# OLD_REGENIX_Relais.net
KiCad netlist of a schematic drawn in Altium Designer
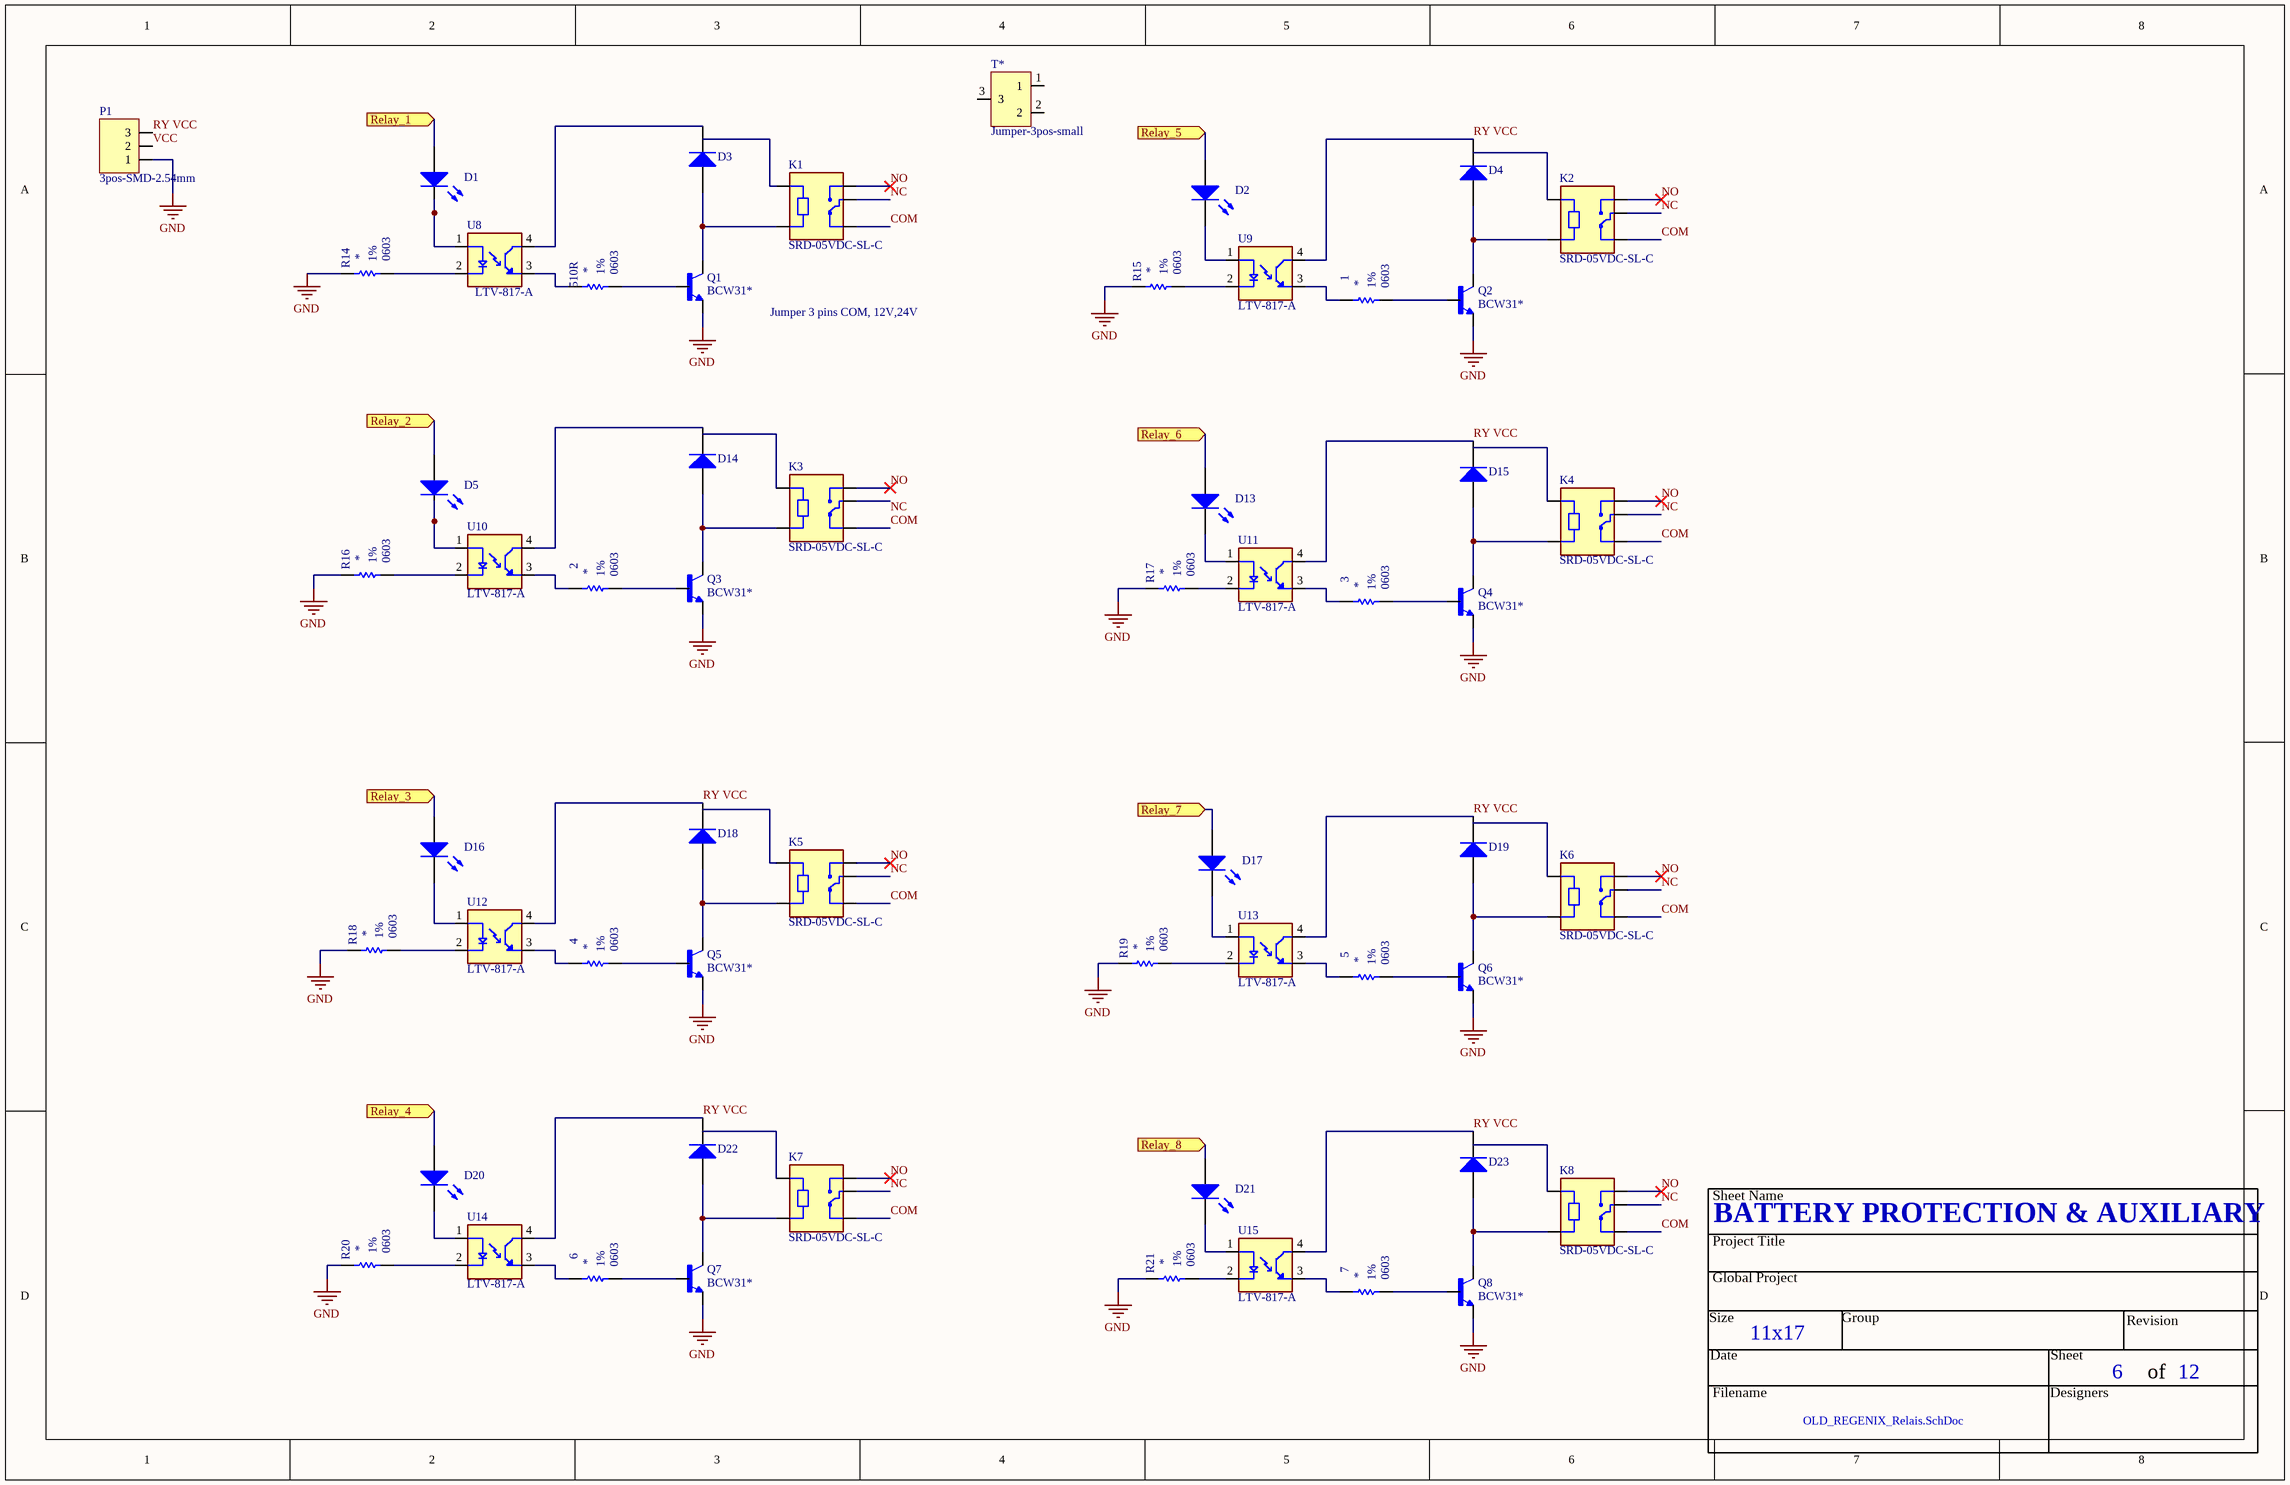
[diagram p0: OLD_REGENIX_Relais.SchDoc]

(export (version "E")
  (design (tool "Eeschema 10.0.6"))
  (components
    (comp (ref "1")
      (value "RES - 0603")
      (footprint "RES_0603")
      (fields
        (field (name "PACKAGE") "0603")
        (field (name "PRECISION") "1%")
        (field (name "ALTIUM_VALUE") "*")
        (field (name "CREATEDBY") "Jonathan Bouchard")
      )
      (libsource (lib "S7CAS_LIB2023") (part "RES - 0603"))
    )
    (comp (ref "2")
      (value "RES - 0603")
      (footprint "RES_0603")
      (fields
        (field (name "PACKAGE") "0603")
        (field (name "PRECISION") "1%")
        (field (name "ALTIUM_VALUE") "*")
        (field (name "CREATEDBY") "Jonathan Bouchard")
      )
      (libsource (lib "S7CAS_LIB2023") (part "RES - 0603"))
    )
    (comp (ref "3")
      (value "RES - 0603")
      (footprint "RES_0603")
      (fields
        (field (name "PACKAGE") "0603")
        (field (name "PRECISION") "1%")
        (field (name "ALTIUM_VALUE") "*")
        (field (name "CREATEDBY") "Jonathan Bouchard")
      )
      (libsource (lib "S7CAS_LIB2023") (part "RES - 0603"))
    )
    (comp (ref "4")
      (value "RES - 0603")
      (footprint "RES_0603")
      (fields
        (field (name "PACKAGE") "0603")
        (field (name "PRECISION") "1%")
        (field (name "ALTIUM_VALUE") "*")
        (field (name "CREATEDBY") "Jonathan Bouchard")
      )
      (libsource (lib "S7CAS_LIB2023") (part "RES - 0603"))
    )
    (comp (ref "5")
      (value "RES - 0603")
      (footprint "RES_0603")
      (fields
        (field (name "PACKAGE") "0603")
        (field (name "PRECISION") "1%")
        (field (name "ALTIUM_VALUE") "*")
        (field (name "CREATEDBY") "Jonathan Bouchard")
      )
      (libsource (lib "S7CAS_LIB2023") (part "RES - 0603"))
    )
    (comp (ref "6")
      (value "RES - 0603")
      (footprint "RES_0603")
      (fields
        (field (name "PACKAGE") "0603")
        (field (name "PRECISION") "1%")
        (field (name "ALTIUM_VALUE") "*")
        (field (name "CREATEDBY") "Jonathan Bouchard")
      )
      (libsource (lib "S7CAS_LIB2023") (part "RES - 0603"))
    )
    (comp (ref "7")
      (value "RES - 0603")
      (footprint "RES_0603")
      (fields
        (field (name "PACKAGE") "0603")
        (field (name "PRECISION") "1%")
        (field (name "ALTIUM_VALUE") "*")
        (field (name "CREATEDBY") "Jonathan Bouchard")
      )
      (libsource (lib "S7CAS_LIB2023") (part "RES - 0603"))
    )
    (comp (ref "510R")
      (value "RES - 0603")
      (footprint "RES_0603")
      (fields
        (field (name "PACKAGE") "0603")
        (field (name "PRECISION") "1%")
        (field (name "ALTIUM_VALUE") "*")
        (field (name "CREATEDBY") "Jonathan Bouchard")
      )
      (libsource (lib "S7CAS_LIB2023") (part "RES - 0603"))
    )
    (comp (ref "D1")
      (value "Light-Emitting Diode")
      (libsource (lib "Simulation Generic Components") (part "LED"))
    )
    (comp (ref "D2")
      (value "Light-Emitting Diode")
      (libsource (lib "Simulation Generic Components") (part "LED"))
    )
    (comp (ref "D3") (value "Diode") (libsource (lib "Simulation Generic Components") (part "Diode")))
    (comp (ref "D4") (value "Diode") (libsource (lib "Simulation Generic Components") (part "Diode")))
    (comp (ref "D5")
      (value "Light-Emitting Diode")
      (libsource (lib "Simulation Generic Components") (part "LED"))
    )
    (comp (ref "D13")
      (value "Light-Emitting Diode")
      (libsource (lib "Simulation Generic Components") (part "LED"))
    )
    (comp (ref "D14") (value "Diode") (libsource (lib "Simulation Generic Components") (part "Diode")))
    (comp (ref "D15") (value "Diode") (libsource (lib "Simulation Generic Components") (part "Diode")))
    (comp (ref "D16")
      (value "Light-Emitting Diode")
      (libsource (lib "Simulation Generic Components") (part "LED"))
    )
    (comp (ref "D17")
      (value "Light-Emitting Diode")
      (libsource (lib "Simulation Generic Components") (part "LED"))
    )
    (comp (ref "D18") (value "Diode") (libsource (lib "Simulation Generic Components") (part "Diode")))
    (comp (ref "D19") (value "Diode") (libsource (lib "Simulation Generic Components") (part "Diode")))
    (comp (ref "D20")
      (value "Light-Emitting Diode")
      (libsource (lib "Simulation Generic Components") (part "LED"))
    )
    (comp (ref "D21")
      (value "Light-Emitting Diode")
      (libsource (lib "Simulation Generic Components") (part "LED"))
    )
    (comp (ref "D22") (value "Diode") (libsource (lib "Simulation Generic Components") (part "Diode")))
    (comp (ref "D23") (value "Diode") (libsource (lib "Simulation Generic Components") (part "Diode")))
    (comp (ref "K1")
      (value "SRD-05VDC-SL-C")
      (footprint "RELAY_SRD-05VDC-SL-C")
      (fields (field (name "MF") "Songle Relay"))
      (libsource (lib "SRD-05VDC-SL-C") (part "SRD-05VDC-SL-C"))
    )
    (comp (ref "K2")
      (value "SRD-05VDC-SL-C")
      (footprint "RELAY_SRD-05VDC-SL-C")
      (fields (field (name "MF") "Songle Relay"))
      (libsource (lib "SRD-05VDC-SL-C") (part "SRD-05VDC-SL-C"))
    )
    (comp (ref "K3")
      (value "SRD-05VDC-SL-C")
      (footprint "RELAY_SRD-05VDC-SL-C")
      (fields (field (name "MF") "Songle Relay"))
      (libsource (lib "SRD-05VDC-SL-C") (part "SRD-05VDC-SL-C"))
    )
    (comp (ref "K4")
      (value "SRD-05VDC-SL-C")
      (footprint "RELAY_SRD-05VDC-SL-C")
      (fields (field (name "MF") "Songle Relay"))
      (libsource (lib "SRD-05VDC-SL-C") (part "SRD-05VDC-SL-C"))
    )
    (comp (ref "K5")
      (value "SRD-05VDC-SL-C")
      (footprint "RELAY_SRD-05VDC-SL-C")
      (fields (field (name "MF") "Songle Relay"))
      (libsource (lib "SRD-05VDC-SL-C") (part "SRD-05VDC-SL-C"))
    )
    (comp (ref "K6")
      (value "SRD-05VDC-SL-C")
      (footprint "RELAY_SRD-05VDC-SL-C")
      (fields (field (name "MF") "Songle Relay"))
      (libsource (lib "SRD-05VDC-SL-C") (part "SRD-05VDC-SL-C"))
    )
    (comp (ref "K7")
      (value "SRD-05VDC-SL-C")
      (footprint "RELAY_SRD-05VDC-SL-C")
      (fields (field (name "MF") "Songle Relay"))
      (libsource (lib "SRD-05VDC-SL-C") (part "SRD-05VDC-SL-C"))
    )
    (comp (ref "K8")
      (value "SRD-05VDC-SL-C")
      (footprint "RELAY_SRD-05VDC-SL-C")
      (fields (field (name "MF") "Songle Relay"))
      (libsource (lib "SRD-05VDC-SL-C") (part "SRD-05VDC-SL-C"))
    )
    (comp (ref "P1")
      (value "3pos-SMD-2.54mm")
      (footprint "HDR1X3 - PAD")
      (description "3pos SMD 2.54mm Header")
      (libsource (lib "main_lib") (part "3pos-SMD-2.54mm_1"))
    )
    (comp (ref "Q1")
      (value "BCW31*")
      (footprint "SOT23-BEC")
      (fields (field (name "MF") "Fairchild Semiconductor") (field (name "MP") "BCW31"))
      (libsource (lib "BCW31_") (part "BCW31*"))
    )
    (comp (ref "Q2")
      (value "BCW31*")
      (footprint "SOT23-BEC")
      (fields (field (name "MF") "Fairchild Semiconductor") (field (name "MP") "BCW31"))
      (libsource (lib "BCW31_") (part "BCW31*"))
    )
    (comp (ref "Q3")
      (value "BCW31*")
      (footprint "SOT23-BEC")
      (fields (field (name "MF") "Fairchild Semiconductor") (field (name "MP") "BCW31"))
      (libsource (lib "BCW31_") (part "BCW31*"))
    )
    (comp (ref "Q4")
      (value "BCW31*")
      (footprint "SOT23-BEC")
      (fields (field (name "MF") "Fairchild Semiconductor") (field (name "MP") "BCW31"))
      (libsource (lib "BCW31_") (part "BCW31*"))
    )
    (comp (ref "Q5")
      (value "BCW31*")
      (footprint "SOT23-BEC")
      (fields (field (name "MF") "Fairchild Semiconductor") (field (name "MP") "BCW31"))
      (libsource (lib "BCW31_") (part "BCW31*"))
    )
    (comp (ref "Q6")
      (value "BCW31*")
      (footprint "SOT23-BEC")
      (fields (field (name "MF") "Fairchild Semiconductor") (field (name "MP") "BCW31"))
      (libsource (lib "BCW31_") (part "BCW31*"))
    )
    (comp (ref "Q7")
      (value "BCW31*")
      (footprint "SOT23-BEC")
      (fields (field (name "MF") "Fairchild Semiconductor") (field (name "MP") "BCW31"))
      (libsource (lib "BCW31_") (part "BCW31*"))
    )
    (comp (ref "Q8")
      (value "BCW31*")
      (footprint "SOT23-BEC")
      (fields (field (name "MF") "Fairchild Semiconductor") (field (name "MP") "BCW31"))
      (libsource (lib "BCW31_") (part "BCW31*"))
    )
    (comp (ref "R14")
      (value "RES - 0603")
      (footprint "RES_0603")
      (fields
        (field (name "PACKAGE") "0603")
        (field (name "PRECISION") "1%")
        (field (name "ALTIUM_VALUE") "*")
        (field (name "CREATEDBY") "Jonathan Bouchard")
      )
      (libsource (lib "S7CAS_LIB2023") (part "RES - 0603"))
    )
    (comp (ref "R15")
      (value "RES - 0603")
      (footprint "RES_0603")
      (fields
        (field (name "PACKAGE") "0603")
        (field (name "PRECISION") "1%")
        (field (name "ALTIUM_VALUE") "*")
        (field (name "CREATEDBY") "Jonathan Bouchard")
      )
      (libsource (lib "S7CAS_LIB2023") (part "RES - 0603"))
    )
    (comp (ref "R16")
      (value "RES - 0603")
      (footprint "RES_0603")
      (fields
        (field (name "PACKAGE") "0603")
        (field (name "PRECISION") "1%")
        (field (name "ALTIUM_VALUE") "*")
        (field (name "CREATEDBY") "Jonathan Bouchard")
      )
      (libsource (lib "S7CAS_LIB2023") (part "RES - 0603"))
    )
    (comp (ref "R17")
      (value "RES - 0603")
      (footprint "RES_0603")
      (fields
        (field (name "PACKAGE") "0603")
        (field (name "PRECISION") "1%")
        (field (name "ALTIUM_VALUE") "*")
        (field (name "CREATEDBY") "Jonathan Bouchard")
      )
      (libsource (lib "S7CAS_LIB2023") (part "RES - 0603"))
    )
    (comp (ref "R18")
      (value "RES - 0603")
      (footprint "RES_0603")
      (fields
        (field (name "PACKAGE") "0603")
        (field (name "PRECISION") "1%")
        (field (name "ALTIUM_VALUE") "*")
        (field (name "CREATEDBY") "Jonathan Bouchard")
      )
      (libsource (lib "S7CAS_LIB2023") (part "RES - 0603"))
    )
    (comp (ref "R19")
      (value "RES - 0603")
      (footprint "RES_0603")
      (fields
        (field (name "PACKAGE") "0603")
        (field (name "PRECISION") "1%")
        (field (name "ALTIUM_VALUE") "*")
        (field (name "CREATEDBY") "Jonathan Bouchard")
      )
      (libsource (lib "S7CAS_LIB2023") (part "RES - 0603"))
    )
    (comp (ref "R20")
      (value "RES - 0603")
      (footprint "RES_0603")
      (fields
        (field (name "PACKAGE") "0603")
        (field (name "PRECISION") "1%")
        (field (name "ALTIUM_VALUE") "*")
        (field (name "CREATEDBY") "Jonathan Bouchard")
      )
      (libsource (lib "S7CAS_LIB2023") (part "RES - 0603"))
    )
    (comp (ref "R21")
      (value "RES - 0603")
      (footprint "RES_0603")
      (fields
        (field (name "PACKAGE") "0603")
        (field (name "PRECISION") "1%")
        (field (name "ALTIUM_VALUE") "*")
        (field (name "CREATEDBY") "Jonathan Bouchard")
      )
      (libsource (lib "S7CAS_LIB2023") (part "RES - 0603"))
    )
    (comp (ref "T*")
      (value "Jumper-3pos-small")
      (footprint "Jumper-3pos-small")
      (libsource (lib "main_lib") (part "Jumper-3pos-small"))
    )
    (comp (ref "U8")
      (value "LTV-817-A")
      (footprint "DIP762W50P254L510H500Q4")
      (description "Optoisolator Transistor Output 5000Vrms 1 Channel 4-DIP")
      (fields (field (name "MF") "Lite-On Inc."))
      (libsource (lib "LTV-817-A") (part "LTV-817-A"))
    )
    (comp (ref "U9")
      (value "LTV-817-A")
      (footprint "DIP762W50P254L510H500Q4")
      (description "Optoisolator Transistor Output 5000Vrms 1 Channel 4-DIP")
      (fields (field (name "MF") "Lite-On Inc."))
      (libsource (lib "LTV-817-A") (part "LTV-817-A"))
    )
    (comp (ref "U10")
      (value "LTV-817-A")
      (footprint "DIP762W50P254L510H500Q4")
      (description "Optoisolator Transistor Output 5000Vrms 1 Channel 4-DIP")
      (fields (field (name "MF") "Lite-On Inc."))
      (libsource (lib "LTV-817-A") (part "LTV-817-A"))
    )
    (comp (ref "U11")
      (value "LTV-817-A")
      (footprint "DIP762W50P254L510H500Q4")
      (description "Optoisolator Transistor Output 5000Vrms 1 Channel 4-DIP")
      (fields (field (name "MF") "Lite-On Inc."))
      (libsource (lib "LTV-817-A") (part "LTV-817-A"))
    )
    (comp (ref "U12")
      (value "LTV-817-A")
      (footprint "DIP762W50P254L510H500Q4")
      (description "Optoisolator Transistor Output 5000Vrms 1 Channel 4-DIP")
      (fields (field (name "MF") "Lite-On Inc."))
      (libsource (lib "LTV-817-A") (part "LTV-817-A"))
    )
    (comp (ref "U13")
      (value "LTV-817-A")
      (footprint "DIP762W50P254L510H500Q4")
      (description "Optoisolator Transistor Output 5000Vrms 1 Channel 4-DIP")
      (fields (field (name "MF") "Lite-On Inc."))
      (libsource (lib "LTV-817-A") (part "LTV-817-A"))
    )
    (comp (ref "U14")
      (value "LTV-817-A")
      (footprint "DIP762W50P254L510H500Q4")
      (description "Optoisolator Transistor Output 5000Vrms 1 Channel 4-DIP")
      (fields (field (name "MF") "Lite-On Inc."))
      (libsource (lib "LTV-817-A") (part "LTV-817-A"))
    )
    (comp (ref "U15")
      (value "LTV-817-A")
      (footprint "DIP762W50P254L510H500Q4")
      (description "Optoisolator Transistor Output 5000Vrms 1 Channel 4-DIP")
      (fields (field (name "MF") "Lite-On Inc."))
      (libsource (lib "LTV-817-A") (part "LTV-817-A"))
    )
  )
  (nets
    (net (code "1") (name "/COM") (class "Default")
      (node (ref "K1") (pin "NC") (pinfunction "NC_NC") (pintype "passive"))
      (node (ref "K2") (pin "NC") (pinfunction "NC_NC") (pintype "passive"))
      (node (ref "K3") (pin "NC") (pinfunction "NC_NC") (pintype "passive"))
      (node (ref "K4") (pin "NC") (pinfunction "NC_NC") (pintype "passive"))
      (node (ref "K5") (pin "NC") (pinfunction "NC_NC") (pintype "passive"))
      (node (ref "K6") (pin "NC") (pinfunction "NC_NC") (pintype "passive"))
      (node (ref "K7") (pin "NC") (pinfunction "NC_NC") (pintype "passive"))
      (node (ref "K8") (pin "NC") (pinfunction "NC_NC") (pintype "passive"))
    )
    (net (code "2") (name "/NC") (class "Default")
      (node (ref "K1") (pin "COM") (pinfunction "COM_COM") (pintype "passive"))
      (node (ref "K2") (pin "COM") (pinfunction "COM_COM") (pintype "passive"))
      (node (ref "K4") (pin "COM") (pinfunction "COM_COM") (pintype "passive"))
      (node (ref "K5") (pin "COM") (pinfunction "COM_COM") (pintype "passive"))
      (node (ref "K6") (pin "COM") (pinfunction "COM_COM") (pintype "passive"))
      (node (ref "K7") (pin "COM") (pinfunction "COM_COM") (pintype "passive"))
      (node (ref "K8") (pin "COM") (pinfunction "COM_COM") (pintype "passive"))
    )
    (net (code "3") (name "/NO") (class "Default")
      (node (ref "K1") (pin "NO") (pinfunction "NO_NO") (pintype "passive"))
      (node (ref "K2") (pin "NO") (pinfunction "NO_NO") (pintype "passive"))
      (node (ref "K3") (pin "NO") (pinfunction "NO_NO") (pintype "passive"))
      (node (ref "K4") (pin "NO") (pinfunction "NO_NO") (pintype "passive"))
      (node (ref "K5") (pin "NO") (pinfunction "NO_NO") (pintype "passive"))
      (node (ref "K6") (pin "NO") (pinfunction "NO_NO") (pintype "passive"))
      (node (ref "K7") (pin "NO") (pinfunction "NO_NO") (pintype "passive"))
      (node (ref "K8") (pin "NO") (pinfunction "NO_NO") (pintype "passive"))
    )
    (net (code "4") (name "/RY VCC") (class "Default")
      (node (ref "D15") (pin "2") (pinfunction "K_2") (pintype "passive"))
      (node (ref "D18") (pin "2") (pinfunction "K_2") (pintype "passive"))
      (node (ref "D19") (pin "2") (pinfunction "K_2") (pintype "passive"))
      (node (ref "D22") (pin "2") (pinfunction "K_2") (pintype "passive"))
      (node (ref "D23") (pin "2") (pinfunction "K_2") (pintype "passive"))
      (node (ref "D4") (pin "2") (pinfunction "K_2") (pintype "passive"))
      (node (ref "P1") (pin "3") (pinfunction "3_3") (pintype "passive"))
      (node (ref "U11") (pin "4") (pinfunction "CT_4") (pintype "passive"))
      (node (ref "U12") (pin "4") (pinfunction "CT_4") (pintype "passive"))
      (node (ref "U13") (pin "4") (pinfunction "CT_4") (pintype "passive"))
      (node (ref "U14") (pin "4") (pinfunction "CT_4") (pintype "passive"))
      (node (ref "U15") (pin "4") (pinfunction "CT_4") (pintype "passive"))
      (node (ref "U9") (pin "4") (pinfunction "CT_4") (pintype "passive"))
    )
    (net (code "5") (name "/Relay_1") (class "Default")
      (node (ref "D1") (pin "1") (pinfunction "A_1") (pintype "passive"))
    )
    (net (code "6") (name "/Relay_2") (class "Default")
      (node (ref "D5") (pin "1") (pinfunction "A_1") (pintype "passive"))
    )
    (net (code "7") (name "/Relay_3") (class "Default")
      (node (ref "D16") (pin "1") (pinfunction "A_1") (pintype "passive"))
    )
    (net (code "8") (name "/Relay_4") (class "Default")
      (node (ref "D20") (pin "1") (pinfunction "A_1") (pintype "passive"))
    )
    (net (code "9") (name "/Relay_5") (class "Default")
      (node (ref "D2") (pin "1") (pinfunction "A_1") (pintype "passive"))
    )
    (net (code "10") (name "/Relay_6") (class "Default")
      (node (ref "D13") (pin "1") (pinfunction "A_1") (pintype "passive"))
    )
    (net (code "11") (name "/Relay_7") (class "Default")
      (node (ref "D17") (pin "1") (pinfunction "A_1") (pintype "passive"))
    )
    (net (code "12") (name "/Relay_8") (class "Default")
      (node (ref "D21") (pin "1") (pinfunction "A_1") (pintype "passive"))
    )
    (net (code "13") (name "/VCC") (class "Default")
      (node (ref "P1") (pin "2") (pinfunction "2_2") (pintype "passive"))
    )
    (net (code "14") (name "GND") (class "Default")
      (node (ref "P1") (pin "1") (pinfunction "1_1") (pintype "passive"))
      (node (ref "Q1") (pin "E") (pinfunction "E_E") (pintype "passive"))
      (node (ref "Q2") (pin "E") (pinfunction "E_E") (pintype "passive"))
      (node (ref "Q3") (pin "E") (pinfunction "E_E") (pintype "passive"))
      (node (ref "Q4") (pin "E") (pinfunction "E_E") (pintype "passive"))
      (node (ref "Q5") (pin "E") (pinfunction "E_E") (pintype "passive"))
      (node (ref "Q6") (pin "E") (pinfunction "E_E") (pintype "passive"))
      (node (ref "Q7") (pin "E") (pinfunction "E_E") (pintype "passive"))
      (node (ref "Q8") (pin "E") (pinfunction "E_E") (pintype "passive"))
      (node (ref "R14") (pin "2") (pinfunction "2_2") (pintype "passive"))
      (node (ref "R15") (pin "2") (pinfunction "2_2") (pintype "passive"))
      (node (ref "R16") (pin "2") (pinfunction "2_2") (pintype "passive"))
      (node (ref "R17") (pin "2") (pinfunction "2_2") (pintype "passive"))
      (node (ref "R18") (pin "2") (pinfunction "2_2") (pintype "passive"))
      (node (ref "R19") (pin "2") (pinfunction "2_2") (pintype "passive"))
      (node (ref "R20") (pin "2") (pinfunction "2_2") (pintype "passive"))
      (node (ref "R21") (pin "2") (pinfunction "2_2") (pintype "passive"))
    )
    (net (code "15") (name "Net-(1-Pad1)") (class "Default")
      (node (ref "1") (pin "1") (pinfunction "1_1") (pintype "passive"))
      (node (ref "Q2") (pin "B") (pinfunction "B_B") (pintype "passive"))
    )
    (net (code "16") (name "Net-(2-Pad1)") (class "Default")
      (node (ref "2") (pin "1") (pinfunction "1_1") (pintype "passive"))
      (node (ref "Q3") (pin "B") (pinfunction "B_B") (pintype "passive"))
    )
    (net (code "17") (name "Net-(3-Pad1)") (class "Default")
      (node (ref "3") (pin "1") (pinfunction "1_1") (pintype "passive"))
      (node (ref "Q4") (pin "B") (pinfunction "B_B") (pintype "passive"))
    )
    (net (code "18") (name "Net-(4-Pad1)") (class "Default")
      (node (ref "4") (pin "1") (pinfunction "1_1") (pintype "passive"))
      (node (ref "Q5") (pin "B") (pinfunction "B_B") (pintype "passive"))
    )
    (net (code "19") (name "Net-(5-Pad1)") (class "Default")
      (node (ref "5") (pin "1") (pinfunction "1_1") (pintype "passive"))
      (node (ref "Q6") (pin "B") (pinfunction "B_B") (pintype "passive"))
    )
    (net (code "20") (name "Net-(6-Pad1)") (class "Default")
      (node (ref "6") (pin "1") (pinfunction "1_1") (pintype "passive"))
      (node (ref "Q7") (pin "B") (pinfunction "B_B") (pintype "passive"))
    )
    (net (code "21") (name "Net-(7-Pad1)") (class "Default")
      (node (ref "7") (pin "1") (pinfunction "1_1") (pintype "passive"))
      (node (ref "Q8") (pin "B") (pinfunction "B_B") (pintype "passive"))
    )
    (net (code "22") (name "Net-(510R-Pad1)") (class "Default")
      (node (ref "510R") (pin "1") (pinfunction "1_1") (pintype "passive"))
      (node (ref "Q1") (pin "B") (pinfunction "B_B") (pintype "passive"))
    )
    (net (code "23") (name "Net-(D1-K)") (class "Default")
      (node (ref "D1") (pin "2") (pinfunction "K_2") (pintype "passive"))
      (node (ref "U8") (pin "1") (pinfunction "A_1") (pintype "passive"))
    )
    (net (code "24") (name "Net-(D2-K)") (class "Default")
      (node (ref "D2") (pin "2") (pinfunction "K_2") (pintype "passive"))
      (node (ref "U9") (pin "1") (pinfunction "A_1") (pintype "passive"))
    )
    (net (code "25") (name "Net-(D3-A)") (class "Default")
      (node (ref "D3") (pin "1") (pinfunction "A_1") (pintype "passive"))
      (node (ref "K1") (pin "A2") (pinfunction "A2_A2") (pintype "passive"))
      (node (ref "Q1") (pin "C") (pinfunction "C_C") (pintype "passive"))
    )
    (net (code "26") (name "Net-(D3-K)") (class "Default")
      (node (ref "D3") (pin "2") (pinfunction "K_2") (pintype "passive"))
      (node (ref "U8") (pin "4") (pinfunction "CT_4") (pintype "passive"))
    )
    (net (code "27") (name "Net-(D4-A)") (class "Default")
      (node (ref "D4") (pin "1") (pinfunction "A_1") (pintype "passive"))
      (node (ref "K2") (pin "A2") (pinfunction "A2_A2") (pintype "passive"))
      (node (ref "Q2") (pin "C") (pinfunction "C_C") (pintype "passive"))
    )
    (net (code "28") (name "Net-(D5-K)") (class "Default")
      (node (ref "D5") (pin "2") (pinfunction "K_2") (pintype "passive"))
      (node (ref "U10") (pin "1") (pinfunction "A_1") (pintype "passive"))
    )
    (net (code "29") (name "Net-(D13-K)") (class "Default")
      (node (ref "D13") (pin "2") (pinfunction "K_2") (pintype "passive"))
      (node (ref "U11") (pin "1") (pinfunction "A_1") (pintype "passive"))
    )
    (net (code "30") (name "Net-(D14-A)") (class "Default")
      (node (ref "D14") (pin "1") (pinfunction "A_1") (pintype "passive"))
      (node (ref "K3") (pin "A2") (pinfunction "A2_A2") (pintype "passive"))
      (node (ref "Q3") (pin "C") (pinfunction "C_C") (pintype "passive"))
    )
    (net (code "31") (name "Net-(D14-K)") (class "Default")
      (node (ref "D14") (pin "2") (pinfunction "K_2") (pintype "passive"))
      (node (ref "U10") (pin "4") (pinfunction "CT_4") (pintype "passive"))
    )
    (net (code "32") (name "Net-(D15-A)") (class "Default")
      (node (ref "D15") (pin "1") (pinfunction "A_1") (pintype "passive"))
      (node (ref "K4") (pin "A2") (pinfunction "A2_A2") (pintype "passive"))
      (node (ref "Q4") (pin "C") (pinfunction "C_C") (pintype "passive"))
    )
    (net (code "33") (name "Net-(D16-K)") (class "Default")
      (node (ref "D16") (pin "2") (pinfunction "K_2") (pintype "passive"))
      (node (ref "U12") (pin "1") (pinfunction "A_1") (pintype "passive"))
    )
    (net (code "34") (name "Net-(D17-K)") (class "Default")
      (node (ref "D17") (pin "2") (pinfunction "K_2") (pintype "passive"))
      (node (ref "U13") (pin "1") (pinfunction "A_1") (pintype "passive"))
    )
    (net (code "35") (name "Net-(D18-A)") (class "Default")
      (node (ref "D18") (pin "1") (pinfunction "A_1") (pintype "passive"))
      (node (ref "K5") (pin "A2") (pinfunction "A2_A2") (pintype "passive"))
      (node (ref "Q5") (pin "C") (pinfunction "C_C") (pintype "passive"))
    )
    (net (code "36") (name "Net-(D19-A)") (class "Default")
      (node (ref "D19") (pin "1") (pinfunction "A_1") (pintype "passive"))
      (node (ref "K6") (pin "A2") (pinfunction "A2_A2") (pintype "passive"))
      (node (ref "Q6") (pin "C") (pinfunction "C_C") (pintype "passive"))
    )
    (net (code "37") (name "Net-(D20-K)") (class "Default")
      (node (ref "D20") (pin "2") (pinfunction "K_2") (pintype "passive"))
      (node (ref "U14") (pin "1") (pinfunction "A_1") (pintype "passive"))
    )
    (net (code "38") (name "Net-(D21-K)") (class "Default")
      (node (ref "D21") (pin "2") (pinfunction "K_2") (pintype "passive"))
      (node (ref "U15") (pin "1") (pinfunction "A_1") (pintype "passive"))
    )
    (net (code "39") (name "Net-(D22-A)") (class "Default")
      (node (ref "D22") (pin "1") (pinfunction "A_1") (pintype "passive"))
      (node (ref "K7") (pin "A2") (pinfunction "A2_A2") (pintype "passive"))
      (node (ref "Q7") (pin "C") (pinfunction "C_C") (pintype "passive"))
    )
    (net (code "40") (name "Net-(D23-A)") (class "Default")
      (node (ref "D23") (pin "1") (pinfunction "A_1") (pintype "passive"))
      (node (ref "K8") (pin "A2") (pinfunction "A2_A2") (pintype "passive"))
      (node (ref "Q8") (pin "C") (pinfunction "C_C") (pintype "passive"))
    )
    (net (code "41") (name "Net-(U8-C)") (class "Default")
      (node (ref "R14") (pin "1") (pinfunction "1_1") (pintype "passive"))
      (node (ref "U8") (pin "2") (pinfunction "C_2") (pintype "passive"))
    )
    (net (code "42") (name "Net-(U8-ET)") (class "Default")
      (node (ref "510R") (pin "2") (pinfunction "2_2") (pintype "passive"))
      (node (ref "U8") (pin "3") (pinfunction "ET_3") (pintype "passive"))
    )
    (net (code "43") (name "Net-(U9-C)") (class "Default")
      (node (ref "R15") (pin "1") (pinfunction "1_1") (pintype "passive"))
      (node (ref "U9") (pin "2") (pinfunction "C_2") (pintype "passive"))
    )
    (net (code "44") (name "Net-(U9-ET)") (class "Default")
      (node (ref "1") (pin "2") (pinfunction "2_2") (pintype "passive"))
      (node (ref "U9") (pin "3") (pinfunction "ET_3") (pintype "passive"))
    )
    (net (code "45") (name "Net-(U10-C)") (class "Default")
      (node (ref "R16") (pin "1") (pinfunction "1_1") (pintype "passive"))
      (node (ref "U10") (pin "2") (pinfunction "C_2") (pintype "passive"))
    )
    (net (code "46") (name "Net-(U10-ET)") (class "Default")
      (node (ref "2") (pin "2") (pinfunction "2_2") (pintype "passive"))
      (node (ref "U10") (pin "3") (pinfunction "ET_3") (pintype "passive"))
    )
    (net (code "47") (name "Net-(U11-C)") (class "Default")
      (node (ref "R17") (pin "1") (pinfunction "1_1") (pintype "passive"))
      (node (ref "U11") (pin "2") (pinfunction "C_2") (pintype "passive"))
    )
    (net (code "48") (name "Net-(U11-ET)") (class "Default")
      (node (ref "3") (pin "2") (pinfunction "2_2") (pintype "passive"))
      (node (ref "U11") (pin "3") (pinfunction "ET_3") (pintype "passive"))
    )
    (net (code "49") (name "Net-(U12-C)") (class "Default")
      (node (ref "R18") (pin "1") (pinfunction "1_1") (pintype "passive"))
      (node (ref "U12") (pin "2") (pinfunction "C_2") (pintype "passive"))
    )
    (net (code "50") (name "Net-(U12-ET)") (class "Default")
      (node (ref "4") (pin "2") (pinfunction "2_2") (pintype "passive"))
      (node (ref "U12") (pin "3") (pinfunction "ET_3") (pintype "passive"))
    )
    (net (code "51") (name "Net-(U13-C)") (class "Default")
      (node (ref "R19") (pin "1") (pinfunction "1_1") (pintype "passive"))
      (node (ref "U13") (pin "2") (pinfunction "C_2") (pintype "passive"))
    )
    (net (code "52") (name "Net-(U13-ET)") (class "Default")
      (node (ref "5") (pin "2") (pinfunction "2_2") (pintype "passive"))
      (node (ref "U13") (pin "3") (pinfunction "ET_3") (pintype "passive"))
    )
    (net (code "53") (name "Net-(U14-C)") (class "Default")
      (node (ref "R20") (pin "1") (pinfunction "1_1") (pintype "passive"))
      (node (ref "U14") (pin "2") (pinfunction "C_2") (pintype "passive"))
    )
    (net (code "54") (name "Net-(U14-ET)") (class "Default")
      (node (ref "6") (pin "2") (pinfunction "2_2") (pintype "passive"))
      (node (ref "U14") (pin "3") (pinfunction "ET_3") (pintype "passive"))
    )
    (net (code "55") (name "Net-(U15-C)") (class "Default")
      (node (ref "R21") (pin "1") (pinfunction "1_1") (pintype "passive"))
      (node (ref "U15") (pin "2") (pinfunction "C_2") (pintype "passive"))
    )
    (net (code "56") (name "Net-(U15-ET)") (class "Default")
      (node (ref "7") (pin "2") (pinfunction "2_2") (pintype "passive"))
      (node (ref "U15") (pin "3") (pinfunction "ET_3") (pintype "passive"))
    )
    (net (code "57") (name "unconnected-(K1-PadA1)") (class "Default")
      (node (ref "K1") (pin "A1") (pinfunction "A1_A1") (pintype "passive"))
    )
    (net (code "58") (name "unconnected-(K2-PadA1)") (class "Default")
      (node (ref "K2") (pin "A1") (pinfunction "A1_A1") (pintype "passive"))
    )
    (net (code "59") (name "unconnected-(K3-PadA1)") (class "Default")
      (node (ref "K3") (pin "A1") (pinfunction "A1_A1") (pintype "passive"))
    )
    (net (code "60") (name "unconnected-(K3-PadCOM)") (class "Default")
      (node (ref "K3") (pin "COM") (pinfunction "COM_COM") (pintype "passive"))
    )
    (net (code "61") (name "unconnected-(K4-PadA1)") (class "Default")
      (node (ref "K4") (pin "A1") (pinfunction "A1_A1") (pintype "passive"))
    )
    (net (code "62") (name "unconnected-(K5-PadA1)") (class "Default")
      (node (ref "K5") (pin "A1") (pinfunction "A1_A1") (pintype "passive"))
    )
    (net (code "63") (name "unconnected-(K6-PadA1)") (class "Default")
      (node (ref "K6") (pin "A1") (pinfunction "A1_A1") (pintype "passive"))
    )
    (net (code "64") (name "unconnected-(K7-PadA1)") (class "Default")
      (node (ref "K7") (pin "A1") (pinfunction "A1_A1") (pintype "passive"))
    )
    (net (code "65") (name "unconnected-(K8-PadA1)") (class "Default")
      (node (ref "K8") (pin "A1") (pinfunction "A1_A1") (pintype "passive"))
    )
    (net (code "66") (name "unconnected-(T*-Pad1)") (class "Default")
      (node (ref "T*") (pin "1") (pinfunction "1_1") (pintype "passive"))
    )
    (net (code "67") (name "unconnected-(T*-Pad2)") (class "Default")
      (node (ref "T*") (pin "2") (pinfunction "2_2") (pintype "passive"))
    )
    (net (code "68") (name "unconnected-(T*-Pad3)") (class "Default")
      (node (ref "T*") (pin "3") (pinfunction "3_3") (pintype "passive"))
    )
  )
)
